# LED_Pattern_Rod_Project.net
KiCad netlist of a schematic drawn in Altium Designer
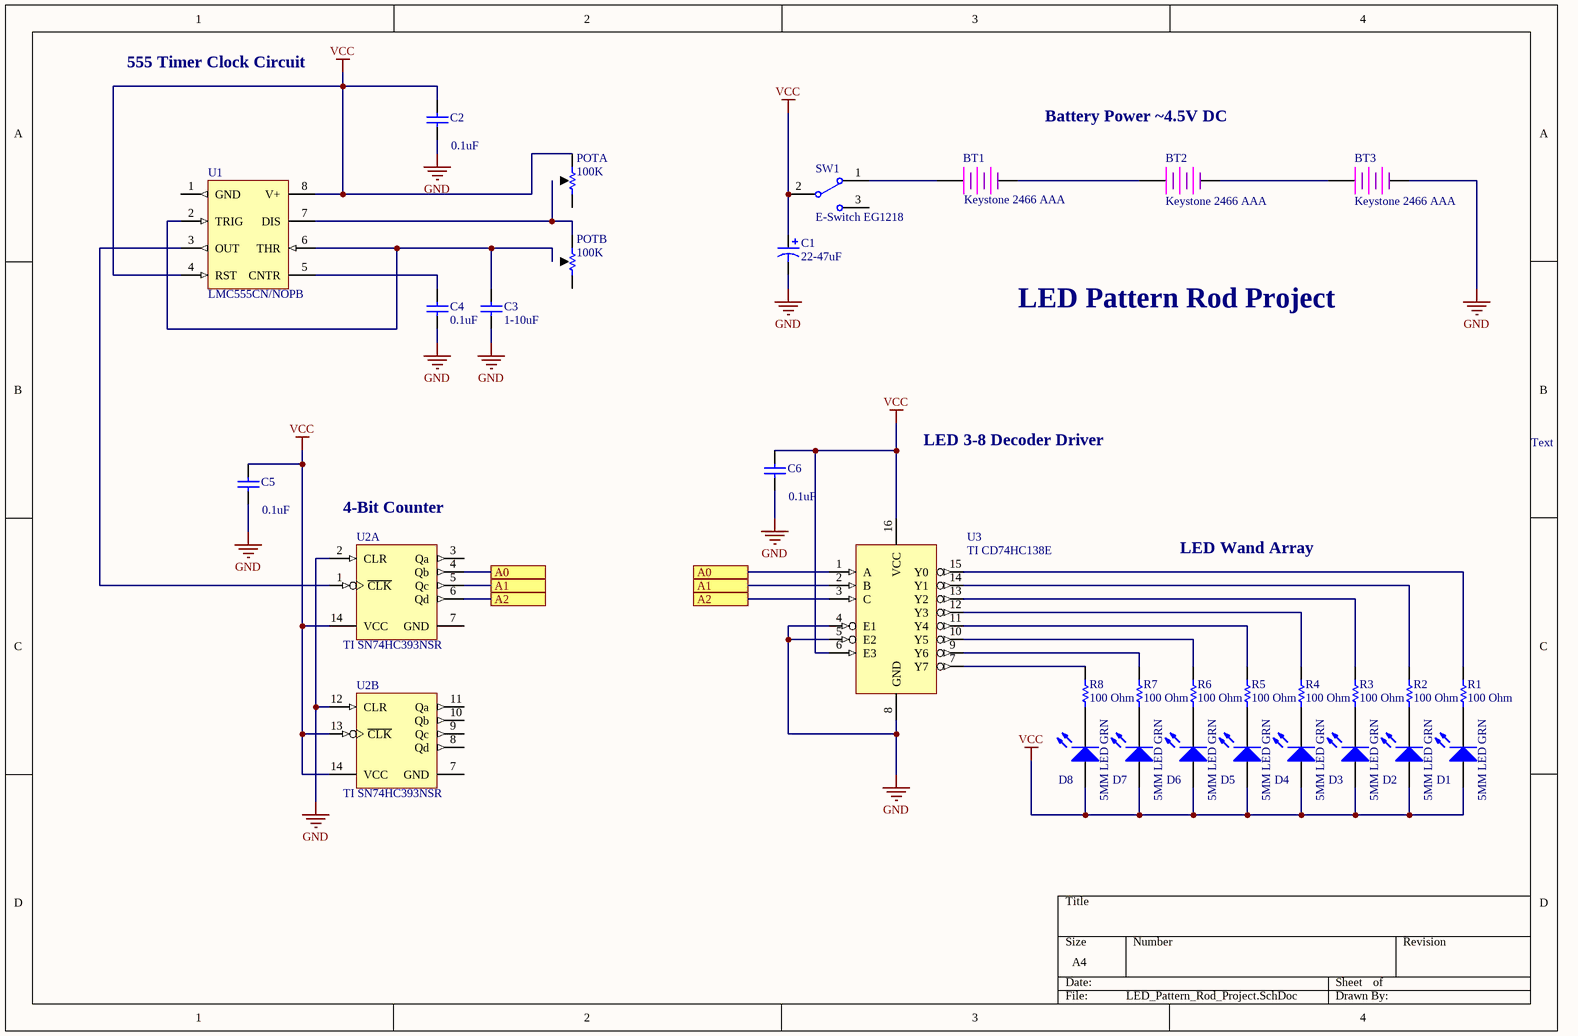
[diagram p0: LED_Pattern_Rod_Project.SchDoc]

(export (version "E")
  (design (tool "Eeschema 10.0.6"))
  (components
    (comp (ref "BT1")
      (value "Keystone 2466 AAA")
      (footprint "PCB-2466")
      (description "Battery holder, AAA, 1 cell, PC mount")
      (libsource (lib "My Personal Space") (part "SYM-2466"))
    )
    (comp (ref "BT2")
      (value "Keystone 2466 AAA")
      (footprint "PCB-2466")
      (description "Battery holder, AAA, 1 cell, PC mount")
      (libsource (lib "My Personal Space") (part "SYM-2466"))
    )
    (comp (ref "BT3")
      (value "Keystone 2466 AAA")
      (footprint "PCB-2466")
      (description "Battery holder, AAA, 1 cell, PC mount")
      (libsource (lib "My Personal Space") (part "SYM-2466"))
    )
    (comp (ref "C1")
      (value "22-47uF")
      (footprint "PCB-nq6yd78wv7rl8ojp8omb-1")
      (description "Cap Aluminum 10uF 16V 20% (4 X 7mm) Cylindrical 18mA 7000 hr 105°C T/R")
      (fields (field (name "MANUFACTURER PART NUMBER") "UCB1C100MCL1GS"))
      (libsource (lib "My Personal Space") (part "SYM-119dd9bbe86bce5a-1"))
    )
    (comp (ref "C2")
      (value "0.1uF")
      (footprint "PCB-ql28fbuo3tond8refhb5-1")
      (description "K 100nF Ceramic Multilayer Capacitor, 50 V dc, +125degC, X7R Dielectric, +/-10%")
      (libsource (lib "My Personal Space") (part "SYM-1272d9258f2acdb5-2"))
    )
    (comp (ref "C3")
      (value "1-10uF")
      (footprint "PCB-ql28fbuo3tond8refhb5-1")
      (description "K 100nF Ceramic Multilayer Capacitor, 50 V dc, +125degC, X7R Dielectric, +/-10%")
      (libsource (lib "My Personal Space") (part "SYM-1272d9258f2acdb5-2"))
    )
    (comp (ref "C4")
      (value "0.1uF")
      (footprint "PCB-ql28fbuo3tond8refhb5-1")
      (description "K 100nF Ceramic Multilayer Capacitor, 50 V dc, +125degC, X7R Dielectric, +/-10%")
      (libsource (lib "My Personal Space") (part "SYM-1272d9258f2acdb5-2"))
    )
    (comp (ref "C5")
      (value "0.1uF")
      (footprint "PCB-ql28fbuo3tond8refhb5-1")
      (description "K 100nF Ceramic Multilayer Capacitor, 50 V dc, +125degC, X7R Dielectric, +/-10%")
      (libsource (lib "My Personal Space") (part "SYM-1272d9258f2acdb5-2"))
    )
    (comp (ref "C6")
      (value "0.1uF")
      (footprint "PCB-ql28fbuo3tond8refhb5-1")
      (description "K 100nF Ceramic Multilayer Capacitor, 50 V dc, +125degC, X7R Dielectric, +/-10%")
      (libsource (lib "My Personal Space") (part "SYM-1272d9258f2acdb5-2"))
    )
    (comp (ref "D1")
      (value "5MM LED GRN")
      (footprint "PCB-b5vk7vz0xhkw7l0fnova-1")
      (description "LED Uni-Color Green 2-Pin T-1 3/4 Bulk")
      (fields
        (field (name "MANUFACTURER PART NUMBER") "C503B-GCN-CY0C0791")
        (field (name "MANUFACTURER") "Cree")
      )
      (libsource (lib "My Personal Space") (part "SYM-92bb5b2eff764d7c-1"))
    )
    (comp (ref "D2")
      (value "5MM LED GRN")
      (footprint "PCB-b5vk7vz0xhkw7l0fnova-1")
      (description "LED Uni-Color Green 2-Pin T-1 3/4 Bulk")
      (fields
        (field (name "MANUFACTURER PART NUMBER") "C503B-GCN-CY0C0791")
        (field (name "MANUFACTURER") "Cree")
      )
      (libsource (lib "My Personal Space") (part "SYM-92bb5b2eff764d7c-1"))
    )
    (comp (ref "D3")
      (value "5MM LED GRN")
      (footprint "PCB-b5vk7vz0xhkw7l0fnova-1")
      (description "LED Uni-Color Green 2-Pin T-1 3/4 Bulk")
      (fields
        (field (name "MANUFACTURER PART NUMBER") "C503B-GCN-CY0C0791")
        (field (name "MANUFACTURER") "Cree")
      )
      (libsource (lib "My Personal Space") (part "SYM-92bb5b2eff764d7c-1"))
    )
    (comp (ref "D4")
      (value "5MM LED GRN")
      (footprint "PCB-b5vk7vz0xhkw7l0fnova-1")
      (description "LED Uni-Color Green 2-Pin T-1 3/4 Bulk")
      (fields
        (field (name "MANUFACTURER PART NUMBER") "C503B-GCN-CY0C0791")
        (field (name "MANUFACTURER") "Cree")
      )
      (libsource (lib "My Personal Space") (part "SYM-92bb5b2eff764d7c-1"))
    )
    (comp (ref "D5")
      (value "5MM LED GRN")
      (footprint "PCB-b5vk7vz0xhkw7l0fnova-1")
      (description "LED Uni-Color Green 2-Pin T-1 3/4 Bulk")
      (fields
        (field (name "MANUFACTURER PART NUMBER") "C503B-GCN-CY0C0791")
        (field (name "MANUFACTURER") "Cree")
      )
      (libsource (lib "My Personal Space") (part "SYM-92bb5b2eff764d7c-1"))
    )
    (comp (ref "D6")
      (value "5MM LED GRN")
      (footprint "PCB-b5vk7vz0xhkw7l0fnova-1")
      (description "LED Uni-Color Green 2-Pin T-1 3/4 Bulk")
      (fields
        (field (name "MANUFACTURER PART NUMBER") "C503B-GCN-CY0C0791")
        (field (name "MANUFACTURER") "Cree")
      )
      (libsource (lib "My Personal Space") (part "SYM-92bb5b2eff764d7c-1"))
    )
    (comp (ref "D7")
      (value "5MM LED GRN")
      (footprint "PCB-b5vk7vz0xhkw7l0fnova-1")
      (description "LED Uni-Color Green 2-Pin T-1 3/4 Bulk")
      (fields
        (field (name "MANUFACTURER PART NUMBER") "C503B-GCN-CY0C0791")
        (field (name "MANUFACTURER") "Cree")
      )
      (libsource (lib "My Personal Space") (part "SYM-92bb5b2eff764d7c-1"))
    )
    (comp (ref "D8")
      (value "5MM LED GRN")
      (footprint "PCB-b5vk7vz0xhkw7l0fnova-1")
      (description "LED Uni-Color Green 2-Pin T-1 3/4 Bulk")
      (fields
        (field (name "MANUFACTURER PART NUMBER") "C503B-GCN-CY0C0791")
        (field (name "MANUFACTURER") "Cree")
      )
      (libsource (lib "My Personal Space") (part "SYM-92bb5b2eff764d7c-1"))
    )
    (comp (ref "POTA")
      (value "100K")
      (footprint "PCB-yu8b13vw5bhotm5v9joo-1")
      (description "Res Cermet Trimmer 200K Ohm 10% 1/2W 1(Elec)/1(Mech)Turn 2.6mm (7 X 7 X 5.8mm) Pin Thru-Hole Bulk")
      (fields (field (name "MANUFACTURER PART NUMBER") "CT-6EP204"))
      (libsource (lib "My Personal Space") (part "SYM-1c6ed013efbec3a9-1"))
    )
    (comp (ref "POTB")
      (value "100K")
      (footprint "PCB-yu8b13vw5bhotm5v9joo-1")
      (description "Res Cermet Trimmer 200K Ohm 10% 1/2W 1(Elec)/1(Mech)Turn 2.6mm (7 X 7 X 5.8mm) Pin Thru-Hole Bulk")
      (fields (field (name "MANUFACTURER PART NUMBER") "CT-6EP204"))
      (libsource (lib "My Personal Space") (part "SYM-1c6ed013efbec3a9-1"))
    )
    (comp (ref "R1")
      (value "100 Ohm")
      (footprint "PCB-0jk5y5qyb1smy9vf6b7t-1")
      (description "Res, 1K, 250mW, 5%, Axial")
      (libsource (lib "My Personal Space") (part "SYM-db3e1311f37e04f9-4"))
    )
    (comp (ref "R2")
      (value "100 Ohm")
      (footprint "PCB-0jk5y5qyb1smy9vf6b7t-1")
      (description "Res, 1K, 250mW, 5%, Axial")
      (libsource (lib "My Personal Space") (part "SYM-db3e1311f37e04f9-4"))
    )
    (comp (ref "R3")
      (value "100 Ohm")
      (footprint "PCB-0jk5y5qyb1smy9vf6b7t-1")
      (description "Res, 1K, 250mW, 5%, Axial")
      (libsource (lib "My Personal Space") (part "SYM-db3e1311f37e04f9-4"))
    )
    (comp (ref "R4")
      (value "100 Ohm")
      (footprint "PCB-0jk5y5qyb1smy9vf6b7t-1")
      (description "Res, 1K, 250mW, 5%, Axial")
      (libsource (lib "My Personal Space") (part "SYM-db3e1311f37e04f9-4"))
    )
    (comp (ref "R5")
      (value "100 Ohm")
      (footprint "PCB-0jk5y5qyb1smy9vf6b7t-1")
      (description "Res, 1K, 250mW, 5%, Axial")
      (libsource (lib "My Personal Space") (part "SYM-db3e1311f37e04f9-4"))
    )
    (comp (ref "R6")
      (value "100 Ohm")
      (footprint "PCB-0jk5y5qyb1smy9vf6b7t-1")
      (description "Res, 1K, 250mW, 5%, Axial")
      (libsource (lib "My Personal Space") (part "SYM-db3e1311f37e04f9-4"))
    )
    (comp (ref "R7")
      (value "100 Ohm")
      (footprint "PCB-0jk5y5qyb1smy9vf6b7t-1")
      (description "Res, 1K, 250mW, 5%, Axial")
      (libsource (lib "My Personal Space") (part "SYM-db3e1311f37e04f9-4"))
    )
    (comp (ref "R8")
      (value "100 Ohm")
      (footprint "PCB-0jk5y5qyb1smy9vf6b7t-1")
      (description "Res, 1K, 250mW, 5%, Axial")
      (libsource (lib "My Personal Space") (part "SYM-db3e1311f37e04f9-4"))
    )
    (comp (ref "SW1")
      (value "E-Switch EG1218")
      (footprint "ESWI-EG1218_V")
      (description "Slide Switch, 500 V, -20 to 70 degC, 3-Pin THD, RoHS")
      (fields (field (name "MANUFACTURER PART NUMBER") "EG1218"))
      (libsource (lib "My Personal Space") (part "SW-SPDT-3_B"))
    )
    (comp (ref "U1")
      (value "LMC555CN/NOPB")
      (footprint "TI-D8_L")
      (description "World’s smallest 555 timer with low power, high accuracy and a Fmax of 3MHz 8-SOIC -40 to 85")
      (fields (field (name "MANUFACTURER PART NUMBER") "LMC555CMX/NOPB"))
      (libsource (lib "My Personal Space") (part "INF-TLE5012BE5000-PG-DSO-8-16-8"))
    )
    (comp (ref "U2")
      (value "TI SN74HC393NSR")
      (footprint "SOIC-SL14_N")
      (description "Counter/Divider Dual 4-Bit Binary UP 14-Pin SOP T/R   SMD")
      (fields (field (name "MANUFACTURER PART NUMBER") "SN74HC393NSR"))
      (libsource (lib "My Personal Space") (part "SYM-3c53f5596157e394-1"))
    )
    (comp (ref "U3")
      (value "TI CD74HC138E")
      (footprint "PCB-iqyivjlmuk83cucpld0n-1")
      (description "TEXAS INSTRUMENTS   CD74HC138E   Logic Type:Decoder / Demultiplexer")
      (fields
        (field (name "MANUFACTURER") "Texas Instruments")
        (field (name "MANUFACTURER PART NUMBER") "CD74HC138E")
      )
      (libsource (lib "My Personal Space") (part "SYM-1166716-1"))
    )
  )
  (nets
    (net (code "1") (name "/A0") (class "Default")
      (node (ref "U2") (pin "4") (pinfunction "Qb_4") (pintype "output"))
      (node (ref "U3") (pin "1") (pinfunction "A_1") (pintype "input"))
    )
    (net (code "2") (name "/A1") (class "Default")
      (node (ref "U2") (pin "5") (pinfunction "Qc_5") (pintype "output"))
      (node (ref "U3") (pin "2") (pinfunction "B_2") (pintype "input"))
    )
    (net (code "3") (name "/A2") (class "Default")
      (node (ref "U2") (pin "6") (pinfunction "Qd_6") (pintype "output"))
      (node (ref "U3") (pin "3") (pinfunction "C_3") (pintype "input"))
    )
    (net (code "4") (name "GND") (class "Default")
      (node (ref "BT3") (pin "2") (pinfunction "-_2") (pintype "passive"))
      (node (ref "C1") (pin "2") (pinfunction "2_2") (pintype "passive"))
      (node (ref "C2") (pin "1") (pinfunction "1_1") (pintype "passive"))
      (node (ref "C3") (pin "1") (pinfunction "1_1") (pintype "passive"))
      (node (ref "C4") (pin "1") (pinfunction "1_1") (pintype "passive"))
      (node (ref "C5") (pin "1") (pinfunction "1_1") (pintype "passive"))
      (node (ref "C6") (pin "1") (pinfunction "1_1") (pintype "passive"))
      (node (ref "U2") (pin "12") (pinfunction "CLR_12") (pintype "input"))
      (node (ref "U2") (pin "2") (pinfunction "CLR_2") (pintype "input"))
      (node (ref "U3") (pin "4") (pinfunction "E1_4") (pintype "input"))
      (node (ref "U3") (pin "5") (pinfunction "E2_5") (pintype "input"))
      (node (ref "U3") (pin "8") (pinfunction "GND_8") (pintype "power_in"))
    )
    (net (code "5") (name "Net-(BT1-+)") (class "Default")
      (node (ref "BT1") (pin "1") (pinfunction "+_1") (pintype "passive"))
      (node (ref "SW1") (pin "1") (pinfunction "1_1") (pintype "passive"))
    )
    (net (code "6") (name "Net-(BT1--)") (class "Default")
      (node (ref "BT1") (pin "2") (pinfunction "-_2") (pintype "passive"))
      (node (ref "BT2") (pin "1") (pinfunction "+_1") (pintype "passive"))
    )
    (net (code "7") (name "Net-(BT2--)") (class "Default")
      (node (ref "BT2") (pin "2") (pinfunction "-_2") (pintype "passive"))
      (node (ref "BT3") (pin "1") (pinfunction "+_1") (pintype "passive"))
    )
    (net (code "8") (name "Net-(D1-K)") (class "Default")
      (node (ref "D1") (pin "1") (pinfunction "K_1") (pintype "passive"))
      (node (ref "R1") (pin "1") (pinfunction "1_1") (pintype "passive"))
    )
    (net (code "9") (name "Net-(D2-K)") (class "Default")
      (node (ref "D2") (pin "1") (pinfunction "K_1") (pintype "passive"))
      (node (ref "R2") (pin "1") (pinfunction "1_1") (pintype "passive"))
    )
    (net (code "10") (name "Net-(D3-K)") (class "Default")
      (node (ref "D3") (pin "1") (pinfunction "K_1") (pintype "passive"))
      (node (ref "R3") (pin "1") (pinfunction "1_1") (pintype "passive"))
    )
    (net (code "11") (name "Net-(D4-K)") (class "Default")
      (node (ref "D4") (pin "1") (pinfunction "K_1") (pintype "passive"))
      (node (ref "R4") (pin "1") (pinfunction "1_1") (pintype "passive"))
    )
    (net (code "12") (name "Net-(D5-K)") (class "Default")
      (node (ref "D5") (pin "1") (pinfunction "K_1") (pintype "passive"))
      (node (ref "R5") (pin "1") (pinfunction "1_1") (pintype "passive"))
    )
    (net (code "13") (name "Net-(D6-K)") (class "Default")
      (node (ref "D6") (pin "1") (pinfunction "K_1") (pintype "passive"))
      (node (ref "R6") (pin "1") (pinfunction "1_1") (pintype "passive"))
    )
    (net (code "14") (name "Net-(D7-K)") (class "Default")
      (node (ref "D7") (pin "1") (pinfunction "K_1") (pintype "passive"))
      (node (ref "R7") (pin "1") (pinfunction "1_1") (pintype "passive"))
    )
    (net (code "15") (name "Net-(D8-K)") (class "Default")
      (node (ref "D8") (pin "1") (pinfunction "K_1") (pintype "passive"))
      (node (ref "R8") (pin "1") (pinfunction "1_1") (pintype "passive"))
    )
    (net (code "16") (name "Net-(U1-CNTR)") (class "Default")
      (node (ref "C4") (pin "2") (pinfunction "2_2") (pintype "passive"))
      (node (ref "U1") (pin "5") (pinfunction "CNTR_5") (pintype "passive"))
    )
    (net (code "17") (name "Net-(U1-DIS)") (class "Default")
      (node (ref "POTA") (pin "2") (pinfunction "2_2") (pintype "passive"))
      (node (ref "POTB") (pin "1") (pinfunction "1_1") (pintype "passive"))
      (node (ref "U1") (pin "7") (pinfunction "DIS_7") (pintype "passive"))
    )
    (net (code "18") (name "Net-(U1-OUT)") (class "Default")
      (node (ref "U1") (pin "3") (pinfunction "OUT_3") (pintype "output"))
      (node (ref "U2") (pin "1") (pinfunction "~{CLK}_1") (pintype "input"))
    )
    (net (code "19") (name "Net-(U1-THR)") (class "Default")
      (node (ref "C3") (pin "2") (pinfunction "2_2") (pintype "passive"))
      (node (ref "POTB") (pin "2") (pinfunction "2_2") (pintype "passive"))
      (node (ref "U1") (pin "2") (pinfunction "TRIG_2") (pintype "input"))
      (node (ref "U1") (pin "6") (pinfunction "THR_6") (pintype "input"))
    )
    (net (code "20") (name "Net-(U3-Y0)") (class "Default")
      (node (ref "R1") (pin "2") (pinfunction "2_2") (pintype "passive"))
      (node (ref "U3") (pin "15") (pinfunction "Y0_15") (pintype "output"))
    )
    (net (code "21") (name "Net-(U3-Y1)") (class "Default")
      (node (ref "R2") (pin "2") (pinfunction "2_2") (pintype "passive"))
      (node (ref "U3") (pin "14") (pinfunction "Y1_14") (pintype "output"))
    )
    (net (code "22") (name "Net-(U3-Y2)") (class "Default")
      (node (ref "R3") (pin "2") (pinfunction "2_2") (pintype "passive"))
      (node (ref "U3") (pin "13") (pinfunction "Y2_13") (pintype "output"))
    )
    (net (code "23") (name "Net-(U3-Y3)") (class "Default")
      (node (ref "R4") (pin "2") (pinfunction "2_2") (pintype "passive"))
      (node (ref "U3") (pin "12") (pinfunction "Y3_12") (pintype "output"))
    )
    (net (code "24") (name "Net-(U3-Y4)") (class "Default")
      (node (ref "R5") (pin "2") (pinfunction "2_2") (pintype "passive"))
      (node (ref "U3") (pin "11") (pinfunction "Y4_11") (pintype "output"))
    )
    (net (code "25") (name "Net-(U3-Y5)") (class "Default")
      (node (ref "R6") (pin "2") (pinfunction "2_2") (pintype "passive"))
      (node (ref "U3") (pin "10") (pinfunction "Y5_10") (pintype "output"))
    )
    (net (code "26") (name "Net-(U3-Y6)") (class "Default")
      (node (ref "R7") (pin "2") (pinfunction "2_2") (pintype "passive"))
      (node (ref "U3") (pin "9") (pinfunction "Y6_9") (pintype "output"))
    )
    (net (code "27") (name "Net-(U3-Y7)") (class "Default")
      (node (ref "R8") (pin "2") (pinfunction "2_2") (pintype "passive"))
      (node (ref "U3") (pin "7") (pinfunction "Y7_7") (pintype "output"))
    )
    (net (code "28") (name "VCC") (class "Default")
      (node (ref "C1") (pin "1") (pinfunction "1_1") (pintype "passive"))
      (node (ref "C2") (pin "2") (pinfunction "2_2") (pintype "passive"))
      (node (ref "C5") (pin "2") (pinfunction "2_2") (pintype "passive"))
      (node (ref "C6") (pin "2") (pinfunction "2_2") (pintype "passive"))
      (node (ref "D1") (pin "2") (pinfunction "A_2") (pintype "passive"))
      (node (ref "D2") (pin "2") (pinfunction "A_2") (pintype "passive"))
      (node (ref "D3") (pin "2") (pinfunction "A_2") (pintype "passive"))
      (node (ref "D4") (pin "2") (pinfunction "A_2") (pintype "passive"))
      (node (ref "D5") (pin "2") (pinfunction "A_2") (pintype "passive"))
      (node (ref "D6") (pin "2") (pinfunction "A_2") (pintype "passive"))
      (node (ref "D7") (pin "2") (pinfunction "A_2") (pintype "passive"))
      (node (ref "D8") (pin "2") (pinfunction "A_2") (pintype "passive"))
      (node (ref "POTA") (pin "1") (pinfunction "1_1") (pintype "passive"))
      (node (ref "SW1") (pin "2") (pinfunction "COM_2") (pintype "passive"))
      (node (ref "U1") (pin "4") (pinfunction "RST_4") (pintype "input"))
      (node (ref "U1") (pin "8") (pinfunction "V+_8") (pintype "power_in"))
      (node (ref "U2") (pin "13") (pinfunction "~{CLK}_13") (pintype "input"))
      (node (ref "U2") (pin "14") (pinfunction "VCC_14") (pintype "power_in"))
      (node (ref "U3") (pin "16") (pinfunction "VCC_16") (pintype "power_in"))
      (node (ref "U3") (pin "6") (pinfunction "E3_6") (pintype "input"))
    )
    (net (code "29") (name "unconnected-(POTA-Pad3)") (class "Default")
      (node (ref "POTA") (pin "3") (pinfunction "3_3") (pintype "passive"))
    )
    (net (code "30") (name "unconnected-(POTB-Pad3)") (class "Default")
      (node (ref "POTB") (pin "3") (pinfunction "3_3") (pintype "passive"))
    )
    (net (code "31") (name "unconnected-(SW1-Pad3)") (class "Default")
      (node (ref "SW1") (pin "3") (pinfunction "3_3") (pintype "passive"))
    )
    (net (code "32") (name "unconnected-(U1-GND-Pad1)") (class "Default")
      (node (ref "U1") (pin "1") (pinfunction "GND_1") (pintype "output"))
    )
    (net (code "33") (name "unconnected-(U2A-GND-Pad7)") (class "Default")
      (node (ref "U2") (pin "7") (pinfunction "GND_7") (pintype "power_in"))
    )
    (net (code "34") (name "unconnected-(U2A-Qa-Pad3)") (class "Default")
      (node (ref "U2") (pin "3") (pinfunction "Qa_3") (pintype "output"))
    )
    (net (code "35") (name "unconnected-(U2B-GND-Pad7)") (class "Default")
      (node (ref "U2") (pin "7") (pinfunction "GND_7") (pintype "power_in"))
    )
    (net (code "36") (name "unconnected-(U2B-Qa-Pad11)") (class "Default")
      (node (ref "U2") (pin "11") (pinfunction "Qa_11") (pintype "output"))
    )
    (net (code "37") (name "unconnected-(U2B-Qb-Pad10)") (class "Default")
      (node (ref "U2") (pin "10") (pinfunction "Qb_10") (pintype "output"))
    )
    (net (code "38") (name "unconnected-(U2B-Qc-Pad9)") (class "Default")
      (node (ref "U2") (pin "9") (pinfunction "Qc_9") (pintype "output"))
    )
    (net (code "39") (name "unconnected-(U2B-Qd-Pad8)") (class "Default")
      (node (ref "U2") (pin "8") (pinfunction "Qd_8") (pintype "output"))
    )
  )
)
